# uSD_Card_Interface.net
KiCad netlist of a schematic drawn in Altium Designer
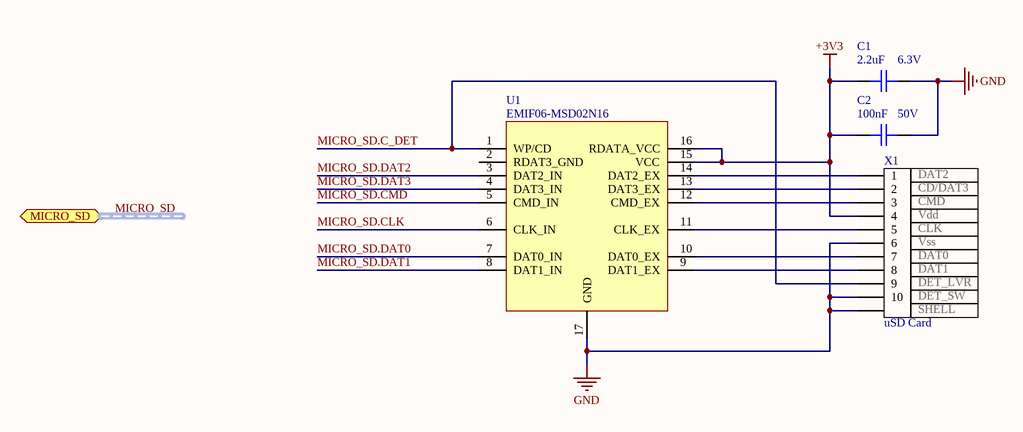
[diagram p0: uSD Card Interface.SchDoc]

(export (version "E")
  (design (tool "Eeschema 10.0.6"))
  (components
    (comp (ref "C1")
      (value "CAP CER 2.2UF 6.3V X5R 0402")
      (footprint "C0402")
      (description "2.2µF ±20% 6.3V Ceramic Capacitor X5R 0402 (1005 Metric)")
      (fields
        (field (name "MANUFACTURER") "Murata")
        (field (name "MANUFACTURER PART NUMBER") "GRM155R60J225ME15D")
        (field (name "CAPACITANCE") "2.2uF")
        (field (name "VOLTAGE") "6.3V")
      )
      (libsource (lib "capacitors_smd") (part "CAP CER 2.2UF 6.3V X5R 0402"))
    )
    (comp (ref "C2")
      (value "CAP CER 0.1UF 50V X7R 0402")
      (footprint "C0402")
      (description "0.1µF ±10% 50V Ceramic Capacitor X7R 0402 (1005 Metric)")
      (fields
        (field (name "MANUFACTURER") "TDK")
        (field (name "MANUFACTURER PART NUMBER") "CGA2B3X7R1H104K050BB")
        (field (name "CAPACITANCE") "100nF")
        (field (name "VOLTAGE") "50V")
      )
      (libsource (lib "capacitors_smd") (part "CAP CER 0.1UF 50V X7R 0402"))
    )
    (comp (ref "U1")
      (value "EMIF06-MSD02N16")
      (footprint "QFN 3.5x1.2-16L")
      (description "RC (Pi) EMI Filter 2nd Order Low Pass 6 Channel R = 45Ohms, C = 20pF (Total)  16-UFDFN Exposed Pad")
      (fields (field (name "MANUFACTURER") "STMicroelectronics"))
      (libsource (lib "diodes_tvs") (part "FILTER RC(PI) 45 OHM/20PF SMD"))
    )
    (comp (ref "X1")
      (value "uSD Card")
      (footprint "5025700893")
      (description "10 (8 + 2) Position Card Connector Secure Digital - microSD™ Surface Mount, Right Angle Gold")
      (fields
        (field (name "MANUFACTURER") "Molex")
        (field (name "MANUFACTURER PART NUMBER") "5025700893")
        (field (name "PIN_1") "DAT2")
        (field (name "PIN_2") "CD/DAT3")
        (field (name "PIN_3") "CMD")
        (field (name "PIN_4") "Vdd")
        (field (name "PIN_5") "CLK")
        (field (name "PIN_6") "Vss")
        (field (name "PIN_7") "DAT0")
        (field (name "PIN_8") "DAT1")
        (field (name "PIN_9") "DET_LVR")
        (field (name "PIN_10") "DET_SW")
        (field (name "PIN_0") "SHELL")
      )
      (libsource (lib "connectors_slots") (part "CONN MICRO SD CARD PUSH-PUSH R/A"))
    )
  )
  (nets
    (net (code "2") (name "+3V3") (class "Default")
      (node (ref "C1") (pin "2") (pinfunction "2_2") (pintype "passive"))
      (node (ref "C2") (pin "2") (pinfunction "2_2") (pintype "passive"))
      (node (ref "U1") (pin "15") (pinfunction "VCC_15") (pintype "power_in"))
      (node (ref "U1") (pin "16") (pinfunction "RDATA_VCC_16") (pintype "power_in"))
      (node (ref "X1") (pin "4") (pinfunction "4_4") (pintype "passive"))
    )
    (net (code "3") (name "/MICRO_SD.CLK") (class "Default")
      (node (ref "U1") (pin "6") (pinfunction "CLK_IN_6") (pintype "passive"))
    )
    (net (code "4") (name "/MICRO_SD.CMD") (class "Default")
      (node (ref "U1") (pin "5") (pinfunction "CMD_IN_5") (pintype "passive"))
    )
    (net (code "5") (name "/MICRO_SD.C_DET") (class "Default")
      (node (ref "U1") (pin "1") (pinfunction "WP/CD_1") (pintype "passive"))
      (node (ref "X1") (pin "9") (pinfunction "9_9") (pintype "passive"))
    )
    (net (code "6") (name "/MICRO_SD.DAT0") (class "Default")
      (node (ref "U1") (pin "7") (pinfunction "DAT0_IN_7") (pintype "passive"))
    )
    (net (code "7") (name "/MICRO_SD.DAT1") (class "Default")
      (node (ref "U1") (pin "8") (pinfunction "DAT1_IN_8") (pintype "passive"))
    )
    (net (code "8") (name "/MICRO_SD.DAT2") (class "Default")
      (node (ref "U1") (pin "3") (pinfunction "DAT2_IN_3") (pintype "passive"))
    )
    (net (code "9") (name "/MICRO_SD.DAT3") (class "Default")
      (node (ref "U1") (pin "4") (pinfunction "DAT3_IN_4") (pintype "passive"))
    )
    (net (code "11") (name "GND") (class "Default")
      (node (ref "C1") (pin "1") (pinfunction "1_1") (pintype "passive"))
      (node (ref "C2") (pin "1") (pinfunction "1_1") (pintype "passive"))
      (node (ref "U1") (pin "17") (pinfunction "GND_17") (pintype "power_in"))
      (node (ref "X1") (pin "0") (pinfunction "0_0") (pintype "power_in"))
      (node (ref "X1") (pin "10") (pinfunction "10_10") (pintype "passive"))
      (node (ref "X1") (pin "6") (pinfunction "6_6") (pintype "passive"))
    )
    (net (code "12") (name "Net-(U1-CLK_EX)") (class "Default")
      (node (ref "U1") (pin "11") (pinfunction "CLK_EX_11") (pintype "passive"))
      (node (ref "X1") (pin "5") (pinfunction "5_5") (pintype "passive"))
    )
    (net (code "13") (name "Net-(U1-CMD_EX)") (class "Default")
      (node (ref "U1") (pin "12") (pinfunction "CMD_EX_12") (pintype "passive"))
      (node (ref "X1") (pin "3") (pinfunction "3_3") (pintype "passive"))
    )
    (net (code "14") (name "Net-(U1-DAT0_EX)") (class "Default")
      (node (ref "U1") (pin "10") (pinfunction "DAT0_EX_10") (pintype "passive"))
      (node (ref "X1") (pin "7") (pinfunction "7_7") (pintype "passive"))
    )
    (net (code "15") (name "Net-(U1-DAT1_EX)") (class "Default")
      (node (ref "U1") (pin "9") (pinfunction "DAT1_EX_9") (pintype "passive"))
      (node (ref "X1") (pin "8") (pinfunction "8_8") (pintype "passive"))
    )
    (net (code "16") (name "Net-(U1-DAT2_EX)") (class "Default")
      (node (ref "U1") (pin "14") (pinfunction "DAT2_EX_14") (pintype "passive"))
      (node (ref "X1") (pin "1") (pinfunction "1_1") (pintype "passive"))
    )
    (net (code "17") (name "Net-(U1-DAT3_EX)") (class "Default")
      (node (ref "U1") (pin "13") (pinfunction "DAT3_EX_13") (pintype "passive"))
      (node (ref "X1") (pin "2") (pinfunction "2_2") (pintype "passive"))
    )
    (net (code "18") (name "unconnected-(U1-RDAT3_GND-Pad2)") (class "Default")
      (node (ref "U1") (pin "2") (pinfunction "RDAT3_GND_2") (pintype "passive"))
    )
  )
)
